# DC_CV_-_SCH.net
KiCad netlist of a schematic drawn in Altium Designer
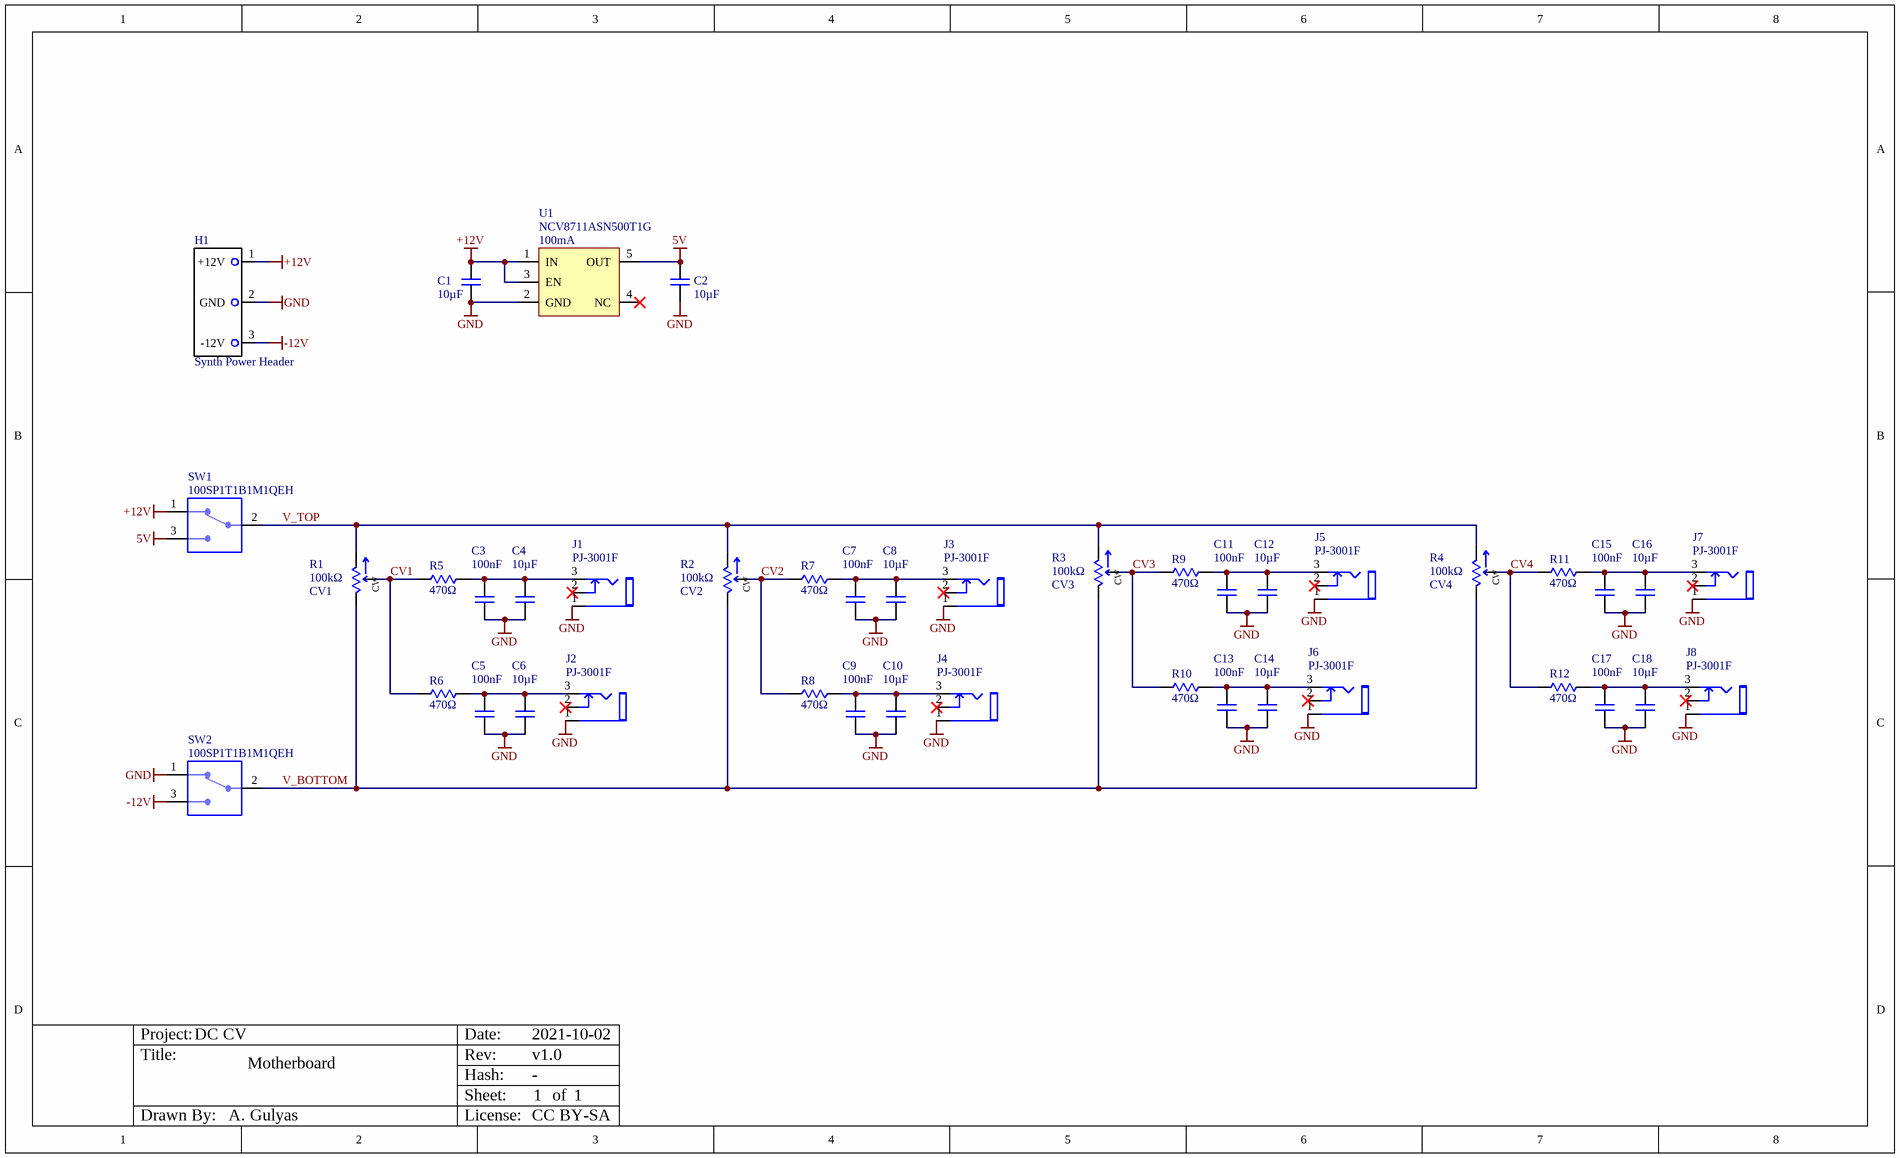
[diagram p0: DC CV - SCH.SchDoc]

(export (version "E")
  (design (tool "Eeschema 10.0.6"))
  (components
    (comp (ref "C1")
      (value "10µF")
      (footprint "0805 - C")
      (description "CAP CER 10UF 16V X5R 0805")
      (fields (field (name "MFG") "Yageo") (field (name "TOLERANCE") "±20%"))
      (libsource (lib "VCA Library") (part "C - 0805 - 10uF - 16V"))
    )
    (comp (ref "C2")
      (value "10µF")
      (footprint "0805 - C")
      (description "CAP CER 10UF 16V X5R 0805")
      (fields (field (name "MFG") "Yageo") (field (name "TOLERANCE") "±20%"))
      (libsource (lib "VCA Library") (part "C - 0805 - 10uF - 16V"))
    )
    (comp (ref "C3")
      (value "100nF")
      (footprint "0603 - C")
      (description "CAP CER 0.1UF 16V X7R 0603")
      (fields (field (name "MFG") "Yageo") (field (name "TOLERANCE") "±10%"))
      (libsource (lib "VCA Library") (part "C - 0603 - 100nF - 16V"))
    )
    (comp (ref "C4")
      (value "10µF")
      (footprint "0805 - C")
      (description "CAP CER 10UF 16V X5R 0805")
      (fields (field (name "MFG") "Yageo") (field (name "TOLERANCE") "±20%"))
      (libsource (lib "VCA Library") (part "C - 0805 - 10uF - 16V"))
    )
    (comp (ref "C5")
      (value "100nF")
      (footprint "0603 - C")
      (description "CAP CER 0.1UF 16V X7R 0603")
      (fields (field (name "MFG") "Yageo") (field (name "TOLERANCE") "±10%"))
      (libsource (lib "VCA Library") (part "C - 0603 - 100nF - 16V"))
    )
    (comp (ref "C6")
      (value "10µF")
      (footprint "0805 - C")
      (description "CAP CER 10UF 16V X5R 0805")
      (fields (field (name "MFG") "Yageo") (field (name "TOLERANCE") "±20%"))
      (libsource (lib "VCA Library") (part "C - 0805 - 10uF - 16V"))
    )
    (comp (ref "C7")
      (value "100nF")
      (footprint "0603 - C")
      (description "CAP CER 0.1UF 16V X7R 0603")
      (fields (field (name "MFG") "Yageo") (field (name "TOLERANCE") "±10%"))
      (libsource (lib "VCA Library") (part "C - 0603 - 100nF - 16V"))
    )
    (comp (ref "C8")
      (value "10µF")
      (footprint "0805 - C")
      (description "CAP CER 10UF 16V X5R 0805")
      (fields (field (name "MFG") "Yageo") (field (name "TOLERANCE") "±20%"))
      (libsource (lib "VCA Library") (part "C - 0805 - 10uF - 16V"))
    )
    (comp (ref "C9")
      (value "100nF")
      (footprint "0603 - C")
      (description "CAP CER 0.1UF 16V X7R 0603")
      (fields (field (name "MFG") "Yageo") (field (name "TOLERANCE") "±10%"))
      (libsource (lib "VCA Library") (part "C - 0603 - 100nF - 16V"))
    )
    (comp (ref "C10")
      (value "10µF")
      (footprint "0805 - C")
      (description "CAP CER 10UF 16V X5R 0805")
      (fields (field (name "MFG") "Yageo") (field (name "TOLERANCE") "±20%"))
      (libsource (lib "VCA Library") (part "C - 0805 - 10uF - 16V"))
    )
    (comp (ref "C11")
      (value "100nF")
      (footprint "0603 - C")
      (description "CAP CER 0.1UF 16V X7R 0603")
      (fields (field (name "MFG") "Yageo") (field (name "TOLERANCE") "±10%"))
      (libsource (lib "VCA Library") (part "C - 0603 - 100nF - 16V"))
    )
    (comp (ref "C12")
      (value "10µF")
      (footprint "0805 - C")
      (description "CAP CER 10UF 16V X5R 0805")
      (fields (field (name "MFG") "Yageo") (field (name "TOLERANCE") "±20%"))
      (libsource (lib "VCA Library") (part "C - 0805 - 10uF - 16V"))
    )
    (comp (ref "C13")
      (value "100nF")
      (footprint "0603 - C")
      (description "CAP CER 0.1UF 16V X7R 0603")
      (fields (field (name "MFG") "Yageo") (field (name "TOLERANCE") "±10%"))
      (libsource (lib "VCA Library") (part "C - 0603 - 100nF - 16V"))
    )
    (comp (ref "C14")
      (value "10µF")
      (footprint "0805 - C")
      (description "CAP CER 10UF 16V X5R 0805")
      (fields (field (name "MFG") "Yageo") (field (name "TOLERANCE") "±20%"))
      (libsource (lib "VCA Library") (part "C - 0805 - 10uF - 16V"))
    )
    (comp (ref "C15")
      (value "100nF")
      (footprint "0603 - C")
      (description "CAP CER 0.1UF 16V X7R 0603")
      (fields (field (name "MFG") "Yageo") (field (name "TOLERANCE") "±10%"))
      (libsource (lib "VCA Library") (part "C - 0603 - 100nF - 16V"))
    )
    (comp (ref "C16")
      (value "10µF")
      (footprint "0805 - C")
      (description "CAP CER 10UF 16V X5R 0805")
      (fields (field (name "MFG") "Yageo") (field (name "TOLERANCE") "±20%"))
      (libsource (lib "VCA Library") (part "C - 0805 - 10uF - 16V"))
    )
    (comp (ref "C17")
      (value "100nF")
      (footprint "0603 - C")
      (description "CAP CER 0.1UF 16V X7R 0603")
      (fields (field (name "MFG") "Yageo") (field (name "TOLERANCE") "±10%"))
      (libsource (lib "VCA Library") (part "C - 0603 - 100nF - 16V"))
    )
    (comp (ref "C18")
      (value "10µF")
      (footprint "0805 - C")
      (description "CAP CER 10UF 16V X5R 0805")
      (fields (field (name "MFG") "Yageo") (field (name "TOLERANCE") "±20%"))
      (libsource (lib "VCA Library") (part "C - 0805 - 10uF - 16V"))
    )
    (comp (ref "H1")
      (value "Synth Power Header")
      (footprint "Eurorack power - 10 pin - DC CV")
      (description "CONN HEADER VERT 10POS 2.54MM")
      (fields (field (name "MFG") "3M"))
      (libsource (lib "Synth UI") (part "H - Synth Power"))
    )
    (comp (ref "J1")
      (value "PJ-3001F")
      (footprint "Jack - TS - PJ-3001F")
      (description "3.5MM MONO PHONE JACK WITH SWITCH")
      (fields (field (name "MFG") "Tayda Electronics"))
      (libsource (lib "VCA Library") (part "Jack - TS - PJ-3001F"))
    )
    (comp (ref "J2")
      (value "PJ-3001F")
      (footprint "Jack - TS - PJ-3001F")
      (description "3.5MM MONO PHONE JACK WITH SWITCH")
      (fields (field (name "MFG") "Tayda Electronics"))
      (libsource (lib "VCA Library") (part "Jack - TS - PJ-3001F"))
    )
    (comp (ref "J3")
      (value "PJ-3001F")
      (footprint "Jack - TS - PJ-3001F")
      (description "3.5MM MONO PHONE JACK WITH SWITCH")
      (fields (field (name "MFG") "Tayda Electronics"))
      (libsource (lib "VCA Library") (part "Jack - TS - PJ-3001F"))
    )
    (comp (ref "J4")
      (value "PJ-3001F")
      (footprint "Jack - TS - PJ-3001F")
      (description "3.5MM MONO PHONE JACK WITH SWITCH")
      (fields (field (name "MFG") "Tayda Electronics"))
      (libsource (lib "VCA Library") (part "Jack - TS - PJ-3001F"))
    )
    (comp (ref "J5")
      (value "PJ-3001F")
      (footprint "Jack - TS - PJ-3001F")
      (description "3.5MM MONO PHONE JACK WITH SWITCH")
      (fields (field (name "MFG") "Tayda Electronics"))
      (libsource (lib "VCA Library") (part "Jack - TS - PJ-3001F"))
    )
    (comp (ref "J6")
      (value "PJ-3001F")
      (footprint "Jack - TS - PJ-3001F")
      (description "3.5MM MONO PHONE JACK WITH SWITCH")
      (fields (field (name "MFG") "Tayda Electronics"))
      (libsource (lib "VCA Library") (part "Jack - TS - PJ-3001F"))
    )
    (comp (ref "J7")
      (value "PJ-3001F")
      (footprint "Jack - TS - PJ-3001F")
      (description "3.5MM MONO PHONE JACK WITH SWITCH")
      (fields (field (name "MFG") "Tayda Electronics"))
      (libsource (lib "VCA Library") (part "Jack - TS - PJ-3001F"))
    )
    (comp (ref "J8")
      (value "PJ-3001F")
      (footprint "Jack - TS - PJ-3001F")
      (description "3.5MM MONO PHONE JACK WITH SWITCH")
      (fields (field (name "MFG") "Tayda Electronics"))
      (libsource (lib "VCA Library") (part "Jack - TS - PJ-3001F"))
    )
    (comp (ref "R1")
      (value "100kΩ")
      (footprint "Pot - P0915N")
      (description "POT 100K OHM 1/20W PLASTIC LIN")
      (fields
        (field (name "MFG") "TT Electronics")
        (field (name "TOLERANCE") "±20%")
        (field (name "PURPOSE") "CV1")
      )
      (libsource (lib "Synth UI") (part "R - pot - 100k"))
    )
    (comp (ref "R2")
      (value "100kΩ")
      (footprint "Pot - P0915N")
      (description "POT 100K OHM 1/20W PLASTIC LIN")
      (fields
        (field (name "MFG") "TT Electronics")
        (field (name "TOLERANCE") "±20%")
        (field (name "PURPOSE") "CV2")
      )
      (libsource (lib "Synth UI") (part "R - pot - 100k"))
    )
    (comp (ref "R3")
      (value "100kΩ")
      (footprint "Pot - P0915N")
      (description "POT 100K OHM 1/20W PLASTIC LIN")
      (fields
        (field (name "MFG") "TT Electronics")
        (field (name "TOLERANCE") "±20%")
        (field (name "PURPOSE") "CV3")
      )
      (libsource (lib "Synth UI") (part "R - pot - 100k"))
    )
    (comp (ref "R4")
      (value "100kΩ")
      (footprint "Pot - P0915N")
      (description "POT 100K OHM 1/20W PLASTIC LIN")
      (fields
        (field (name "MFG") "TT Electronics")
        (field (name "TOLERANCE") "±20%")
        (field (name "PURPOSE") "CV4")
      )
      (libsource (lib "Synth UI") (part "R - pot - 100k"))
    )
    (comp (ref "R5")
      (value "470Ω")
      (footprint "0603 - R")
      (description "RES SMD 470 OHM 5% 1/10W 0603")
      (fields (field (name "MFG") "Yageo") (field (name "POWER") "0.1W"))
      (libsource (lib "VCA Library") (part "R - 0603 - 470R"))
    )
    (comp (ref "R6")
      (value "470Ω")
      (footprint "0603 - R")
      (description "RES SMD 470 OHM 5% 1/10W 0603")
      (fields (field (name "MFG") "Yageo") (field (name "POWER") "0.1W"))
      (libsource (lib "VCA Library") (part "R - 0603 - 470R"))
    )
    (comp (ref "R7")
      (value "470Ω")
      (footprint "0603 - R")
      (description "RES SMD 470 OHM 5% 1/10W 0603")
      (fields (field (name "MFG") "Yageo") (field (name "POWER") "0.1W"))
      (libsource (lib "VCA Library") (part "R - 0603 - 470R"))
    )
    (comp (ref "R8")
      (value "470Ω")
      (footprint "0603 - R")
      (description "RES SMD 470 OHM 5% 1/10W 0603")
      (fields (field (name "MFG") "Yageo") (field (name "POWER") "0.1W"))
      (libsource (lib "VCA Library") (part "R - 0603 - 470R"))
    )
    (comp (ref "R9")
      (value "470Ω")
      (footprint "0603 - R")
      (description "RES SMD 470 OHM 5% 1/10W 0603")
      (fields (field (name "MFG") "Yageo") (field (name "POWER") "0.1W"))
      (libsource (lib "VCA Library") (part "R - 0603 - 470R"))
    )
    (comp (ref "R10")
      (value "470Ω")
      (footprint "0603 - R")
      (description "RES SMD 470 OHM 5% 1/10W 0603")
      (fields (field (name "MFG") "Yageo") (field (name "POWER") "0.1W"))
      (libsource (lib "VCA Library") (part "R - 0603 - 470R"))
    )
    (comp (ref "R11")
      (value "470Ω")
      (footprint "0603 - R")
      (description "RES SMD 470 OHM 5% 1/10W 0603")
      (fields (field (name "MFG") "Yageo") (field (name "POWER") "0.1W"))
      (libsource (lib "VCA Library") (part "R - 0603 - 470R"))
    )
    (comp (ref "R12")
      (value "470Ω")
      (footprint "0603 - R")
      (description "RES SMD 470 OHM 5% 1/10W 0603")
      (fields (field (name "MFG") "Yageo") (field (name "POWER") "0.1W"))
      (libsource (lib "VCA Library") (part "R - 0603 - 470R"))
    )
    (comp (ref "SW1")
      (value "100SP1T1B1M1QEH")
      (footprint "SW - 100SP1T1B1M1QEH")
      (description "SWITCH TOGGLE SPDT 5A 120V")
      (fields (field (name "MFG") "E-Switch"))
      (libsource (lib "Adam home") (part "SW - SPDT - toggle - 100SP1T1B1M1QEH"))
    )
    (comp (ref "SW2")
      (value "100SP1T1B1M1QEH")
      (footprint "SW - 100SP1T1B1M1QEH")
      (description "SWITCH TOGGLE SPDT 5A 120V")
      (fields (field (name "MFG") "E-Switch"))
      (libsource (lib "Adam home") (part "SW - SPDT - toggle - 100SP1T1B1M1QEH"))
    )
    (comp (ref "U1")
      (value "NCV8711ASN500T1G")
      (footprint "TSOT 23 5")
      (description "IC REG LINEAR 5V 100MA 5TSOP")
      (fields (field (name "MFG") "onsemi") (field (name "CURRENT - OUTPUT") "100mA"))
      (libsource (lib "Adam home") (part "Reg - Lin - 5V - NCV8711ASN500T1G"))
    )
  )
  (nets
    (net (code "1") (name "+12V") (class "Default")
      (node (ref "C1") (pin "1") (pinfunction "1_1") (pintype "passive"))
      (node (ref "H1") (pin "1") (pinfunction "+12V_1") (pintype "passive"))
      (node (ref "SW1") (pin "1") (pinfunction "1_1") (pintype "passive"))
      (node (ref "U1") (pin "1") (pinfunction "IN_1") (pintype "passive"))
      (node (ref "U1") (pin "3") (pinfunction "EN_3") (pintype "passive"))
    )
    (net (code "2") (name "-12V") (class "Default")
      (node (ref "H1") (pin "3") (pinfunction "-12V_3") (pintype "passive"))
      (node (ref "SW2") (pin "3") (pinfunction "3_3") (pintype "passive"))
    )
    (net (code "3") (name "/CV1") (class "Default")
      (node (ref "R1") (pin "2") (pinfunction "2_2") (pintype "passive"))
      (node (ref "R5") (pin "1") (pinfunction "1_1") (pintype "passive"))
      (node (ref "R6") (pin "1") (pinfunction "1_1") (pintype "passive"))
    )
    (net (code "4") (name "/CV2") (class "Default")
      (node (ref "R2") (pin "2") (pinfunction "2_2") (pintype "passive"))
      (node (ref "R7") (pin "1") (pinfunction "1_1") (pintype "passive"))
      (node (ref "R8") (pin "1") (pinfunction "1_1") (pintype "passive"))
    )
    (net (code "5") (name "/CV3") (class "Default")
      (node (ref "R10") (pin "1") (pinfunction "1_1") (pintype "passive"))
      (node (ref "R3") (pin "2") (pinfunction "2_2") (pintype "passive"))
      (node (ref "R9") (pin "1") (pinfunction "1_1") (pintype "passive"))
    )
    (net (code "6") (name "/CV4") (class "Default")
      (node (ref "R11") (pin "1") (pinfunction "1_1") (pintype "passive"))
      (node (ref "R12") (pin "1") (pinfunction "1_1") (pintype "passive"))
      (node (ref "R4") (pin "2") (pinfunction "2_2") (pintype "passive"))
    )
    (net (code "7") (name "/V_BOTTOM") (class "Default")
      (node (ref "R1") (pin "1") (pinfunction "1_1") (pintype "passive"))
      (node (ref "R2") (pin "1") (pinfunction "1_1") (pintype "passive"))
      (node (ref "R3") (pin "1") (pinfunction "1_1") (pintype "passive"))
      (node (ref "R4") (pin "1") (pinfunction "1_1") (pintype "passive"))
      (node (ref "SW2") (pin "2") (pinfunction "2_2") (pintype "passive"))
    )
    (net (code "8") (name "/V_TOP") (class "Default")
      (node (ref "R1") (pin "3") (pinfunction "3_3") (pintype "passive"))
      (node (ref "R2") (pin "3") (pinfunction "3_3") (pintype "passive"))
      (node (ref "R3") (pin "3") (pinfunction "3_3") (pintype "passive"))
      (node (ref "R4") (pin "3") (pinfunction "3_3") (pintype "passive"))
      (node (ref "SW1") (pin "2") (pinfunction "2_2") (pintype "passive"))
    )
    (net (code "9") (name "5V") (class "Default")
      (node (ref "C2") (pin "1") (pinfunction "1_1") (pintype "passive"))
      (node (ref "SW1") (pin "3") (pinfunction "3_3") (pintype "passive"))
      (node (ref "U1") (pin "5") (pinfunction "OUT_5") (pintype "passive"))
    )
    (net (code "10") (name "GND") (class "Default")
      (node (ref "C1") (pin "2") (pinfunction "2_2") (pintype "passive"))
      (node (ref "C10") (pin "2") (pinfunction "2_2") (pintype "passive"))
      (node (ref "C11") (pin "2") (pinfunction "2_2") (pintype "passive"))
      (node (ref "C12") (pin "2") (pinfunction "2_2") (pintype "passive"))
      (node (ref "C13") (pin "2") (pinfunction "2_2") (pintype "passive"))
      (node (ref "C14") (pin "2") (pinfunction "2_2") (pintype "passive"))
      (node (ref "C15") (pin "2") (pinfunction "2_2") (pintype "passive"))
      (node (ref "C16") (pin "2") (pinfunction "2_2") (pintype "passive"))
      (node (ref "C17") (pin "2") (pinfunction "2_2") (pintype "passive"))
      (node (ref "C18") (pin "2") (pinfunction "2_2") (pintype "passive"))
      (node (ref "C2") (pin "2") (pinfunction "2_2") (pintype "passive"))
      (node (ref "C3") (pin "2") (pinfunction "2_2") (pintype "passive"))
      (node (ref "C4") (pin "2") (pinfunction "2_2") (pintype "passive"))
      (node (ref "C5") (pin "2") (pinfunction "2_2") (pintype "passive"))
      (node (ref "C6") (pin "2") (pinfunction "2_2") (pintype "passive"))
      (node (ref "C7") (pin "2") (pinfunction "2_2") (pintype "passive"))
      (node (ref "C8") (pin "2") (pinfunction "2_2") (pintype "passive"))
      (node (ref "C9") (pin "2") (pinfunction "2_2") (pintype "passive"))
      (node (ref "H1") (pin "2") (pinfunction "GND_2") (pintype "passive"))
      (node (ref "J1") (pin "1") (pinfunction "1_1") (pintype "passive"))
      (node (ref "J2") (pin "1") (pinfunction "1_1") (pintype "passive"))
      (node (ref "J3") (pin "1") (pinfunction "1_1") (pintype "passive"))
      (node (ref "J4") (pin "1") (pinfunction "1_1") (pintype "passive"))
      (node (ref "J5") (pin "1") (pinfunction "1_1") (pintype "passive"))
      (node (ref "J6") (pin "1") (pinfunction "1_1") (pintype "passive"))
      (node (ref "J7") (pin "1") (pinfunction "1_1") (pintype "passive"))
      (node (ref "J8") (pin "1") (pinfunction "1_1") (pintype "passive"))
      (node (ref "SW2") (pin "1") (pinfunction "1_1") (pintype "passive"))
      (node (ref "U1") (pin "2") (pinfunction "GND_2") (pintype "passive"))
    )
    (net (code "11") (name "Net-(C3-Pad1)") (class "Default")
      (node (ref "C3") (pin "1") (pinfunction "1_1") (pintype "passive"))
      (node (ref "C4") (pin "1") (pinfunction "1_1") (pintype "passive"))
      (node (ref "J1") (pin "3") (pinfunction "3_3") (pintype "passive"))
      (node (ref "R5") (pin "2") (pinfunction "2_2") (pintype "passive"))
    )
    (net (code "12") (name "Net-(C5-Pad1)") (class "Default")
      (node (ref "C5") (pin "1") (pinfunction "1_1") (pintype "passive"))
      (node (ref "C6") (pin "1") (pinfunction "1_1") (pintype "passive"))
      (node (ref "J2") (pin "3") (pinfunction "3_3") (pintype "passive"))
      (node (ref "R6") (pin "2") (pinfunction "2_2") (pintype "passive"))
    )
    (net (code "13") (name "Net-(C7-Pad1)") (class "Default")
      (node (ref "C7") (pin "1") (pinfunction "1_1") (pintype "passive"))
      (node (ref "C8") (pin "1") (pinfunction "1_1") (pintype "passive"))
      (node (ref "J3") (pin "3") (pinfunction "3_3") (pintype "passive"))
      (node (ref "R7") (pin "2") (pinfunction "2_2") (pintype "passive"))
    )
    (net (code "14") (name "Net-(C10-Pad1)") (class "Default")
      (node (ref "C10") (pin "1") (pinfunction "1_1") (pintype "passive"))
      (node (ref "C9") (pin "1") (pinfunction "1_1") (pintype "passive"))
      (node (ref "J4") (pin "3") (pinfunction "3_3") (pintype "passive"))
      (node (ref "R8") (pin "2") (pinfunction "2_2") (pintype "passive"))
    )
    (net (code "15") (name "Net-(C11-Pad1)") (class "Default")
      (node (ref "C11") (pin "1") (pinfunction "1_1") (pintype "passive"))
      (node (ref "C12") (pin "1") (pinfunction "1_1") (pintype "passive"))
      (node (ref "J5") (pin "3") (pinfunction "3_3") (pintype "passive"))
      (node (ref "R9") (pin "2") (pinfunction "2_2") (pintype "passive"))
    )
    (net (code "16") (name "Net-(C13-Pad1)") (class "Default")
      (node (ref "C13") (pin "1") (pinfunction "1_1") (pintype "passive"))
      (node (ref "C14") (pin "1") (pinfunction "1_1") (pintype "passive"))
      (node (ref "J6") (pin "3") (pinfunction "3_3") (pintype "passive"))
      (node (ref "R10") (pin "2") (pinfunction "2_2") (pintype "passive"))
    )
    (net (code "17") (name "Net-(C15-Pad1)") (class "Default")
      (node (ref "C15") (pin "1") (pinfunction "1_1") (pintype "passive"))
      (node (ref "C16") (pin "1") (pinfunction "1_1") (pintype "passive"))
      (node (ref "J7") (pin "3") (pinfunction "3_3") (pintype "passive"))
      (node (ref "R11") (pin "2") (pinfunction "2_2") (pintype "passive"))
    )
    (net (code "18") (name "Net-(C17-Pad1)") (class "Default")
      (node (ref "C17") (pin "1") (pinfunction "1_1") (pintype "passive"))
      (node (ref "C18") (pin "1") (pinfunction "1_1") (pintype "passive"))
      (node (ref "J8") (pin "3") (pinfunction "3_3") (pintype "passive"))
      (node (ref "R12") (pin "2") (pinfunction "2_2") (pintype "passive"))
    )
    (net (code "19") (name "unconnected-(J1-Pad2)") (class "Default")
      (node (ref "J1") (pin "2") (pinfunction "2_2") (pintype "passive+no_connect"))
    )
    (net (code "20") (name "unconnected-(J2-Pad2)") (class "Default")
      (node (ref "J2") (pin "2") (pinfunction "2_2") (pintype "passive+no_connect"))
    )
    (net (code "21") (name "unconnected-(J3-Pad2)") (class "Default")
      (node (ref "J3") (pin "2") (pinfunction "2_2") (pintype "passive+no_connect"))
    )
    (net (code "22") (name "unconnected-(J4-Pad2)") (class "Default")
      (node (ref "J4") (pin "2") (pinfunction "2_2") (pintype "passive+no_connect"))
    )
    (net (code "23") (name "unconnected-(J5-Pad2)") (class "Default")
      (node (ref "J5") (pin "2") (pinfunction "2_2") (pintype "passive+no_connect"))
    )
    (net (code "24") (name "unconnected-(J6-Pad2)") (class "Default")
      (node (ref "J6") (pin "2") (pinfunction "2_2") (pintype "passive+no_connect"))
    )
    (net (code "25") (name "unconnected-(J7-Pad2)") (class "Default")
      (node (ref "J7") (pin "2") (pinfunction "2_2") (pintype "passive+no_connect"))
    )
    (net (code "26") (name "unconnected-(J8-Pad2)") (class "Default")
      (node (ref "J8") (pin "2") (pinfunction "2_2") (pintype "passive+no_connect"))
    )
    (net (code "27") (name "unconnected-(U1-NC-Pad4)") (class "Default")
      (node (ref "U1") (pin "4") (pinfunction "NC_4") (pintype "passive+no_connect"))
    )
  )
)
